# sch_power.net
KiCad netlist of a schematic drawn in Altium Designer
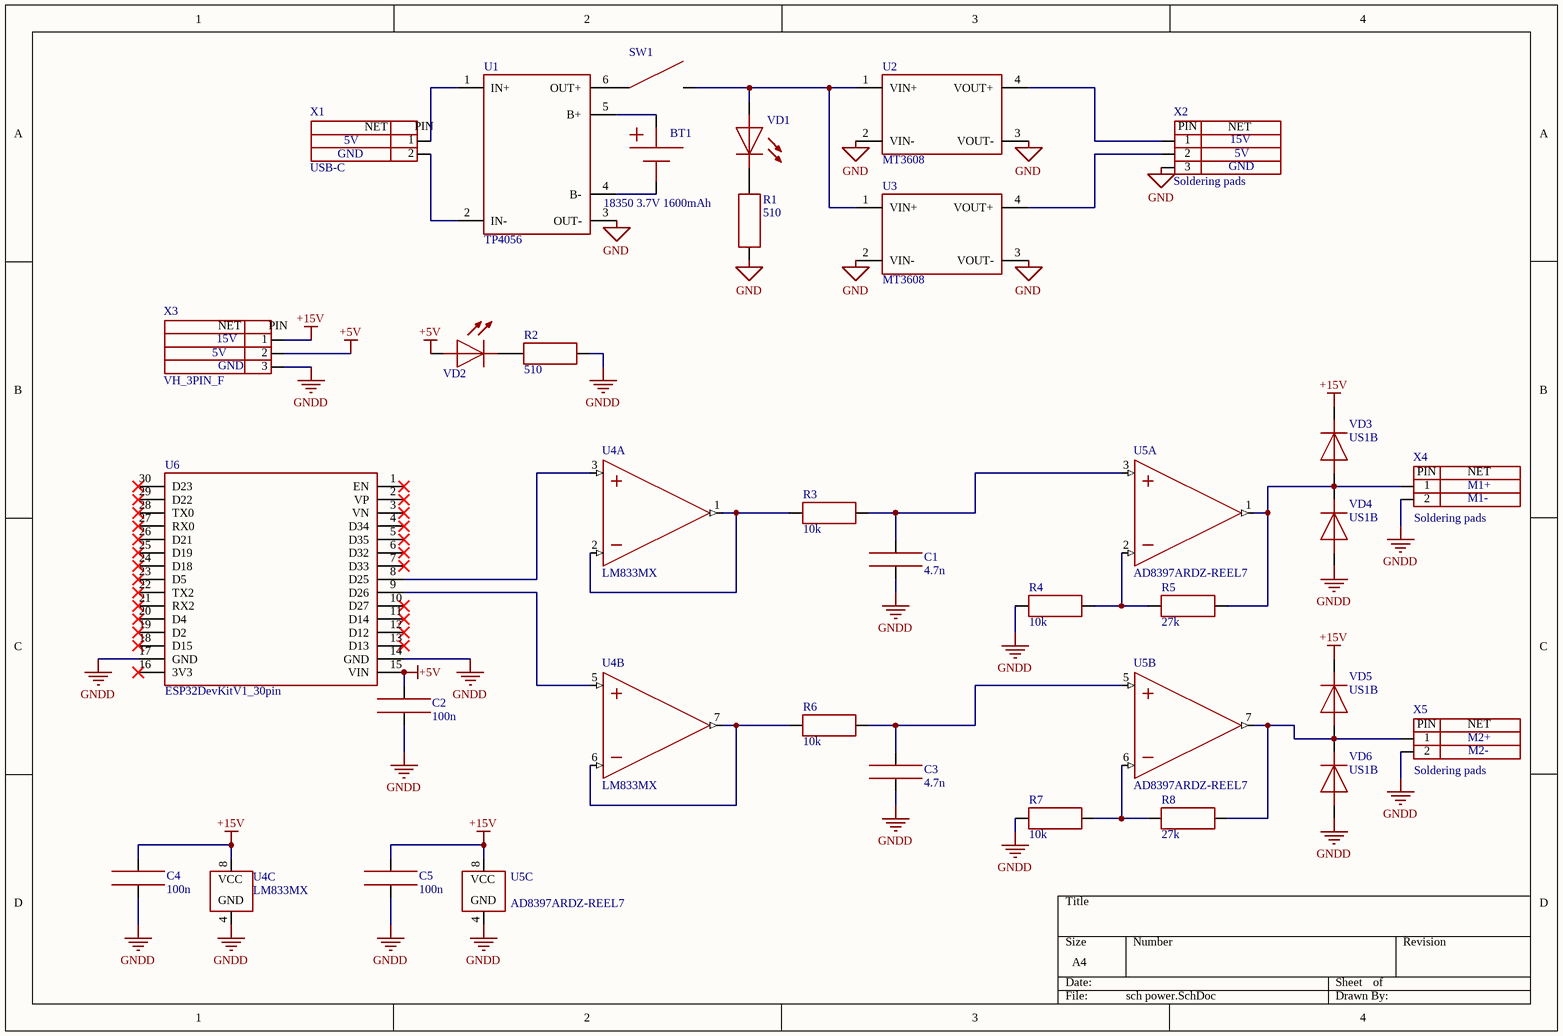
[diagram p0: sch power.SchDoc]

(export (version "E")
  (design (tool "Eeschema 10.0.6"))
  (components
    (comp (ref "BT1") (value "18350 3.7V 1600mAh") (libsource (lib "LeeSch") (part "Battery")))
    (comp (ref "C1")
      (value "4.7n")
      (footprint "C0805")
      (description "MLCC S0R 50V")
      (libsource (lib "LeeSch") (part "Capacitor"))
    )
    (comp (ref "C2")
      (value "100n")
      (footprint "C0805")
      (description "MLCC 50V")
      (libsource (lib "LeeSch") (part "Capacitor"))
    )
    (comp (ref "C3")
      (value "4.7n")
      (footprint "C0805")
      (description "MLCC S0R 50V")
      (libsource (lib "LeeSch") (part "Capacitor"))
    )
    (comp (ref "C4")
      (value "100n")
      (footprint "C0805")
      (description "MLCC 50V")
      (libsource (lib "LeeSch") (part "Capacitor"))
    )
    (comp (ref "C5")
      (value "100n")
      (footprint "C0805")
      (description "MLCC 50V")
      (libsource (lib "LeeSch") (part "Capacitor"))
    )
    (comp (ref "R1") (value "510") (footprint "Res 0.25") (libsource (lib "LeeSch") (part "Resistor")))
    (comp (ref "R2") (value "510") (footprint "R0805") (libsource (lib "") (part "Resistor_2")))
    (comp (ref "R3") (value "10k") (footprint "R0805") (libsource (lib "") (part "Resistor_1")))
    (comp (ref "R4") (value "10k") (footprint "R0805") (libsource (lib "") (part "Resistor_1")))
    (comp (ref "R5") (value "27k") (footprint "R0805") (libsource (lib "") (part "Resistor_1")))
    (comp (ref "R6") (value "10k") (footprint "R0805") (libsource (lib "") (part "Resistor_1")))
    (comp (ref "R7") (value "10k") (footprint "R0805") (libsource (lib "") (part "Resistor_1")))
    (comp (ref "R8") (value "27k") (footprint "R0805") (libsource (lib "") (part "Resistor_1")))
    (comp (ref "SW1")
      (value "Switch (Normal Open, 1 Pole)")
      (libsource (lib "LeeSch") (part "Switch (Normal Open, 1 Pole)"))
    )
    (comp (ref "U1")
      (value "TP4056")
      (description "Charger 3.7V")
      (libsource (lib "LeeSch") (part "MOD_TP4056"))
    )
    (comp (ref "U2")
      (value "MT3608")
      (description "Boost Converter")
      (libsource (lib "LeeSch") (part "MOD_MT3608"))
    )
    (comp (ref "U3")
      (value "MT3608")
      (description "Boost Converter")
      (libsource (lib "LeeSch") (part "MOD_MT3608"))
    )
    (comp (ref "U4")
      (value "LM833MX")
      (footprint "SO8")
      (libsource (lib "LeeSch") (part "IC_OpAmp_LM358 (Dual)"))
    )
    (comp (ref "U5")
      (value "AD8397ARDZ-REEL7")
      (footprint "SOIC-8EP")
      (libsource (lib "LeeSch") (part "IC_OpAmp_LM358 (Dual)"))
    )
    (comp (ref "U6")
      (value "ESP32DevKitV1_30pin")
      (footprint "ESP32 DEVKIT V1_30pin")
      (libsource (lib "LeeSch") (part "MOD_ESP32DevKitV1_30pin"))
    )
    (comp (ref "VD1")
      (value "5003R4D-EPB-P")
      (footprint "2 PIN")
      (libsource (lib "LeeSch") (part "Diode (LED)"))
    )
    (comp (ref "VD2")
      (value "5003R4D-EPB-P")
      (footprint "2 PIN")
      (libsource (lib "LeeSch") (part "Diode (LED)"))
    )
    (comp (ref "VD3") (value "US1B") (footprint "SMA(DO-214AC)") (libsource (lib "LeeSch") (part "Diode")))
    (comp (ref "VD4") (value "US1B") (footprint "SMA(DO-214AC)") (libsource (lib "LeeSch") (part "Diode")))
    (comp (ref "VD5") (value "US1B") (footprint "SMA(DO-214AC)") (libsource (lib "LeeSch") (part "Diode")))
    (comp (ref "VD6") (value "US1B") (footprint "SMA(DO-214AC)") (libsource (lib "LeeSch") (part "Diode")))
    (comp (ref "X1") (value "USB-C") (libsource (lib "") (part "Terminal block (2-pin)_1")))
    (comp (ref "X2") (value "Soldering pads") (libsource (lib "LeeSch") (part "Terminal block (3-pin)")))
    (comp (ref "X3")
      (value "VH_3PIN_F")
      (footprint "VH_3PIN_F")
      (libsource (lib "") (part "Terminal block (3-pin)_1"))
    )
    (comp (ref "X4")
      (value "Soldering pads")
      (footprint "Place 2 (3мм,2мм)")
      (libsource (lib "LeeSch") (part "Terminal block (2-pin)"))
    )
    (comp (ref "X5")
      (value "Soldering pads")
      (footprint "Place 2 (3мм,2мм)")
      (libsource (lib "LeeSch") (part "Terminal block (2-pin)"))
    )
  )
  (nets
    (net (code "1") (name "+5V") (class "Default")
      (node (ref "C2") (pin "2") (pinfunction "2_2") (pintype "passive"))
      (node (ref "U6") (pin "15") (pinfunction "VIN_15") (pintype "power_in"))
      (node (ref "VD2") (pin "1") (pinfunction "Anode_1") (pintype "passive"))
      (node (ref "X3") (pin "2") (pinfunction "NET2_2") (pintype "passive"))
    )
    (net (code "2") (name "+15V") (class "Default")
      (node (ref "C4") (pin "2") (pinfunction "2_2") (pintype "passive"))
      (node (ref "C5") (pin "2") (pinfunction "2_2") (pintype "passive"))
      (node (ref "U4") (pin "8") (pinfunction "VCC_8") (pintype "power_in"))
      (node (ref "U5") (pin "8") (pinfunction "VCC_8") (pintype "power_in"))
      (node (ref "VD3") (pin "2") (pinfunction "Cathode_2") (pintype "passive"))
      (node (ref "VD5") (pin "2") (pinfunction "Cathode_2") (pintype "passive"))
      (node (ref "X3") (pin "1") (pinfunction "NET1_1") (pintype "passive"))
    )
    (net (code "3") (name "GND") (class "Default")
      (node (ref "R1") (pin "1") (pinfunction "1_1") (pintype "passive"))
      (node (ref "U1") (pin "3") (pinfunction "OUT-_3") (pintype "passive"))
      (node (ref "U2") (pin "2") (pinfunction "VIN-_2") (pintype "passive"))
      (node (ref "U2") (pin "3") (pinfunction "VOUT-_3") (pintype "passive"))
      (node (ref "U3") (pin "2") (pinfunction "VIN-_2") (pintype "passive"))
      (node (ref "U3") (pin "3") (pinfunction "VOUT-_3") (pintype "passive"))
      (node (ref "X2") (pin "3") (pinfunction "NET3_3") (pintype "passive"))
    )
    (net (code "4") (name "GNDD") (class "Default")
      (node (ref "C1") (pin "1") (pinfunction "1_1") (pintype "passive"))
      (node (ref "C2") (pin "1") (pinfunction "1_1") (pintype "passive"))
      (node (ref "C3") (pin "1") (pinfunction "1_1") (pintype "passive"))
      (node (ref "C4") (pin "1") (pinfunction "1_1") (pintype "passive"))
      (node (ref "C5") (pin "1") (pinfunction "1_1") (pintype "passive"))
      (node (ref "R2") (pin "1") (pinfunction "1_1") (pintype "passive"))
      (node (ref "R4") (pin "1") (pinfunction "1_1") (pintype "passive"))
      (node (ref "R7") (pin "1") (pinfunction "1_1") (pintype "passive"))
      (node (ref "U4") (pin "4") (pinfunction "GND_4") (pintype "power_in"))
      (node (ref "U5") (pin "4") (pinfunction "GND_4") (pintype "power_in"))
      (node (ref "U6") (pin "14") (pinfunction "GND_14") (pintype "power_in"))
      (node (ref "U6") (pin "17") (pinfunction "GND_17") (pintype "power_in"))
      (node (ref "VD4") (pin "1") (pinfunction "Anode_1") (pintype "passive"))
      (node (ref "VD6") (pin "1") (pinfunction "Anode_1") (pintype "passive"))
      (node (ref "X3") (pin "3") (pinfunction "NET3_3") (pintype "passive"))
      (node (ref "X4") (pin "2") (pinfunction "NET2_2") (pintype "passive"))
      (node (ref "X5") (pin "2") (pinfunction "NET2_2") (pintype "passive"))
    )
    (net (code "5") (name "Net-(BT1-Negative)") (class "Default")
      (node (ref "BT1") (pin "1") (pinfunction "Negative_1") (pintype "passive"))
      (node (ref "U1") (pin "4") (pinfunction "B-_4") (pintype "passive"))
    )
    (net (code "6") (name "Net-(BT1-Positive)") (class "Default")
      (node (ref "BT1") (pin "2") (pinfunction "Positive_2") (pintype "passive"))
      (node (ref "U1") (pin "5") (pinfunction "B+_5") (pintype "passive"))
    )
    (net (code "7") (name "Net-(U1-IN+)") (class "Default")
      (node (ref "U1") (pin "1") (pinfunction "IN+_1") (pintype "passive"))
      (node (ref "X1") (pin "1") (pinfunction "NET1_1") (pintype "passive"))
    )
    (net (code "8") (name "Net-(U1-IN-)") (class "Default")
      (node (ref "U1") (pin "2") (pinfunction "IN-_2") (pintype "passive"))
      (node (ref "X1") (pin "2") (pinfunction "NET2_2") (pintype "passive"))
    )
    (net (code "9") (name "Net-(U1-OUT+)") (class "Default")
      (node (ref "SW1") (pin "1") (pinfunction "1_1") (pintype "passive"))
      (node (ref "U1") (pin "6") (pinfunction "OUT+_6") (pintype "passive"))
    )
    (net (code "10") (name "Net-(U2-VIN+)") (class "Default")
      (node (ref "SW1") (pin "2") (pinfunction "2_2") (pintype "passive"))
      (node (ref "U2") (pin "1") (pinfunction "VIN+_1") (pintype "passive"))
      (node (ref "U3") (pin "1") (pinfunction "VIN+_1") (pintype "passive"))
      (node (ref "VD1") (pin "1") (pinfunction "Anode_1") (pintype "passive"))
    )
    (net (code "11") (name "Net-(U2-VOUT+)") (class "Default")
      (node (ref "U2") (pin "4") (pinfunction "VOUT+_4") (pintype "passive"))
      (node (ref "X2") (pin "1") (pinfunction "NET1_1") (pintype "passive"))
    )
    (net (code "12") (name "Net-(U3-VOUT+)") (class "Default")
      (node (ref "U3") (pin "4") (pinfunction "VOUT+_4") (pintype "passive"))
      (node (ref "X2") (pin "2") (pinfunction "NET2_2") (pintype "passive"))
    )
    (net (code "13") (name "Net-(U4A-1IN+)") (class "Default")
      (node (ref "U4") (pin "3") (pinfunction "1IN+_3") (pintype "input"))
      (node (ref "U6") (pin "8") (pinfunction "D25_8") (pintype "passive"))
    )
    (net (code "14") (name "Net-(U4A-1IN-)") (class "Default")
      (node (ref "R3") (pin "1") (pinfunction "1_1") (pintype "passive"))
      (node (ref "U4") (pin "1") (pinfunction "1OUT_1") (pintype "output"))
      (node (ref "U4") (pin "2") (pinfunction "1IN-_2") (pintype "input"))
    )
    (net (code "15") (name "Net-(U4B-2IN+)") (class "Default")
      (node (ref "U4") (pin "5") (pinfunction "2IN+_5") (pintype "input"))
      (node (ref "U6") (pin "9") (pinfunction "D26_9") (pintype "passive"))
    )
    (net (code "16") (name "Net-(U4B-2IN-)") (class "Default")
      (node (ref "R6") (pin "1") (pinfunction "1_1") (pintype "passive"))
      (node (ref "U4") (pin "6") (pinfunction "2IN-_6") (pintype "input"))
      (node (ref "U4") (pin "7") (pinfunction "2OUT_7") (pintype "output"))
    )
    (net (code "17") (name "Net-(U5A-1IN+)") (class "Default")
      (node (ref "C1") (pin "2") (pinfunction "2_2") (pintype "passive"))
      (node (ref "R3") (pin "2") (pinfunction "2_2") (pintype "passive"))
      (node (ref "U5") (pin "3") (pinfunction "1IN+_3") (pintype "input"))
    )
    (net (code "18") (name "Net-(U5A-1IN-)") (class "Default")
      (node (ref "R4") (pin "2") (pinfunction "2_2") (pintype "passive"))
      (node (ref "R5") (pin "1") (pinfunction "1_1") (pintype "passive"))
      (node (ref "U5") (pin "2") (pinfunction "1IN-_2") (pintype "input"))
    )
    (net (code "19") (name "Net-(U5A-1OUT)") (class "Default")
      (node (ref "R5") (pin "2") (pinfunction "2_2") (pintype "passive"))
      (node (ref "U5") (pin "1") (pinfunction "1OUT_1") (pintype "output"))
      (node (ref "VD3") (pin "1") (pinfunction "Anode_1") (pintype "passive"))
      (node (ref "VD4") (pin "2") (pinfunction "Cathode_2") (pintype "passive"))
      (node (ref "X4") (pin "1") (pinfunction "NET1_1") (pintype "passive"))
    )
    (net (code "20") (name "Net-(U5B-2IN+)") (class "Default")
      (node (ref "C3") (pin "2") (pinfunction "2_2") (pintype "passive"))
      (node (ref "R6") (pin "2") (pinfunction "2_2") (pintype "passive"))
      (node (ref "U5") (pin "5") (pinfunction "2IN+_5") (pintype "input"))
    )
    (net (code "21") (name "Net-(U5B-2IN-)") (class "Default")
      (node (ref "R7") (pin "2") (pinfunction "2_2") (pintype "passive"))
      (node (ref "R8") (pin "1") (pinfunction "1_1") (pintype "passive"))
      (node (ref "U5") (pin "6") (pinfunction "2IN-_6") (pintype "input"))
    )
    (net (code "22") (name "Net-(U5B-2OUT)") (class "Default")
      (node (ref "R8") (pin "2") (pinfunction "2_2") (pintype "passive"))
      (node (ref "U5") (pin "7") (pinfunction "2OUT_7") (pintype "output"))
      (node (ref "VD5") (pin "1") (pinfunction "Anode_1") (pintype "passive"))
      (node (ref "VD6") (pin "2") (pinfunction "Cathode_2") (pintype "passive"))
      (node (ref "X5") (pin "1") (pinfunction "NET1_1") (pintype "passive"))
    )
    (net (code "23") (name "Net-(VD1-Cathode)") (class "Default")
      (node (ref "R1") (pin "2") (pinfunction "2_2") (pintype "passive"))
      (node (ref "VD1") (pin "2") (pinfunction "Cathode_2") (pintype "passive"))
    )
    (net (code "24") (name "Net-(VD2-Cathode)") (class "Default")
      (node (ref "R2") (pin "2") (pinfunction "2_2") (pintype "passive"))
      (node (ref "VD2") (pin "2") (pinfunction "Cathode_2") (pintype "passive"))
    )
    (net (code "25") (name "unconnected-(U6-3V3-Pad16)") (class "Default")
      (node (ref "U6") (pin "16") (pinfunction "3V3_16") (pintype "power_in+no_connect"))
    )
    (net (code "26") (name "unconnected-(U6-D2-Pad19)") (class "Default")
      (node (ref "U6") (pin "19") (pinfunction "D2_19") (pintype "passive+no_connect"))
    )
    (net (code "27") (name "unconnected-(U6-D4-Pad20)") (class "Default")
      (node (ref "U6") (pin "20") (pinfunction "D4_20") (pintype "passive+no_connect"))
    )
    (net (code "28") (name "unconnected-(U6-D5-Pad23)") (class "Default")
      (node (ref "U6") (pin "23") (pinfunction "D5_23") (pintype "passive+no_connect"))
    )
    (net (code "29") (name "unconnected-(U6-D12-Pad12)") (class "Default")
      (node (ref "U6") (pin "12") (pinfunction "D12_12") (pintype "passive+no_connect"))
    )
    (net (code "30") (name "unconnected-(U6-D13-Pad13)") (class "Default")
      (node (ref "U6") (pin "13") (pinfunction "D13_13") (pintype "passive+no_connect"))
    )
    (net (code "31") (name "unconnected-(U6-D14-Pad11)") (class "Default")
      (node (ref "U6") (pin "11") (pinfunction "D14_11") (pintype "passive+no_connect"))
    )
    (net (code "32") (name "unconnected-(U6-D15-Pad18)") (class "Default")
      (node (ref "U6") (pin "18") (pinfunction "D15_18") (pintype "passive+no_connect"))
    )
    (net (code "33") (name "unconnected-(U6-D18-Pad24)") (class "Default")
      (node (ref "U6") (pin "24") (pinfunction "D18_24") (pintype "passive+no_connect"))
    )
    (net (code "34") (name "unconnected-(U6-D19-Pad25)") (class "Default")
      (node (ref "U6") (pin "25") (pinfunction "D19_25") (pintype "passive+no_connect"))
    )
    (net (code "35") (name "unconnected-(U6-D21-Pad26)") (class "Default")
      (node (ref "U6") (pin "26") (pinfunction "D21_26") (pintype "passive+no_connect"))
    )
    (net (code "36") (name "unconnected-(U6-D22-Pad29)") (class "Default")
      (node (ref "U6") (pin "29") (pinfunction "D22_29") (pintype "passive+no_connect"))
    )
    (net (code "37") (name "unconnected-(U6-D23-Pad30)") (class "Default")
      (node (ref "U6") (pin "30") (pinfunction "D23_30") (pintype "passive+no_connect"))
    )
    (net (code "38") (name "unconnected-(U6-D27-Pad10)") (class "Default")
      (node (ref "U6") (pin "10") (pinfunction "D27_10") (pintype "passive+no_connect"))
    )
    (net (code "39") (name "unconnected-(U6-D32-Pad6)") (class "Default")
      (node (ref "U6") (pin "6") (pinfunction "D32_6") (pintype "passive+no_connect"))
    )
    (net (code "40") (name "unconnected-(U6-D33-Pad7)") (class "Default")
      (node (ref "U6") (pin "7") (pinfunction "D33_7") (pintype "passive+no_connect"))
    )
    (net (code "41") (name "unconnected-(U6-D34-Pad4)") (class "Default")
      (node (ref "U6") (pin "4") (pinfunction "D34_4") (pintype "passive+no_connect"))
    )
    (net (code "42") (name "unconnected-(U6-D35-Pad5)") (class "Default")
      (node (ref "U6") (pin "5") (pinfunction "D35_5") (pintype "passive+no_connect"))
    )
    (net (code "43") (name "unconnected-(U6-EN-Pad1)") (class "Default")
      (node (ref "U6") (pin "1") (pinfunction "EN_1") (pintype "passive+no_connect"))
    )
    (net (code "44") (name "unconnected-(U6-RX0-Pad27)") (class "Default")
      (node (ref "U6") (pin "27") (pinfunction "RX0_27") (pintype "passive+no_connect"))
    )
    (net (code "45") (name "unconnected-(U6-RX2-Pad21)") (class "Default")
      (node (ref "U6") (pin "21") (pinfunction "RX2_21") (pintype "passive+no_connect"))
    )
    (net (code "46") (name "unconnected-(U6-TX0-Pad28)") (class "Default")
      (node (ref "U6") (pin "28") (pinfunction "TX0_28") (pintype "passive+no_connect"))
    )
    (net (code "47") (name "unconnected-(U6-TX2-Pad22)") (class "Default")
      (node (ref "U6") (pin "22") (pinfunction "TX2_22") (pintype "passive+no_connect"))
    )
    (net (code "48") (name "unconnected-(U6-VN-Pad3)") (class "Default")
      (node (ref "U6") (pin "3") (pinfunction "VN_3") (pintype "passive+no_connect"))
    )
    (net (code "49") (name "unconnected-(U6-VP-Pad2)") (class "Default")
      (node (ref "U6") (pin "2") (pinfunction "VP_2") (pintype "passive+no_connect"))
    )
  )
)
